# TB906_HW_V1.net
KiCad netlist of a schematic drawn in Altium Designer
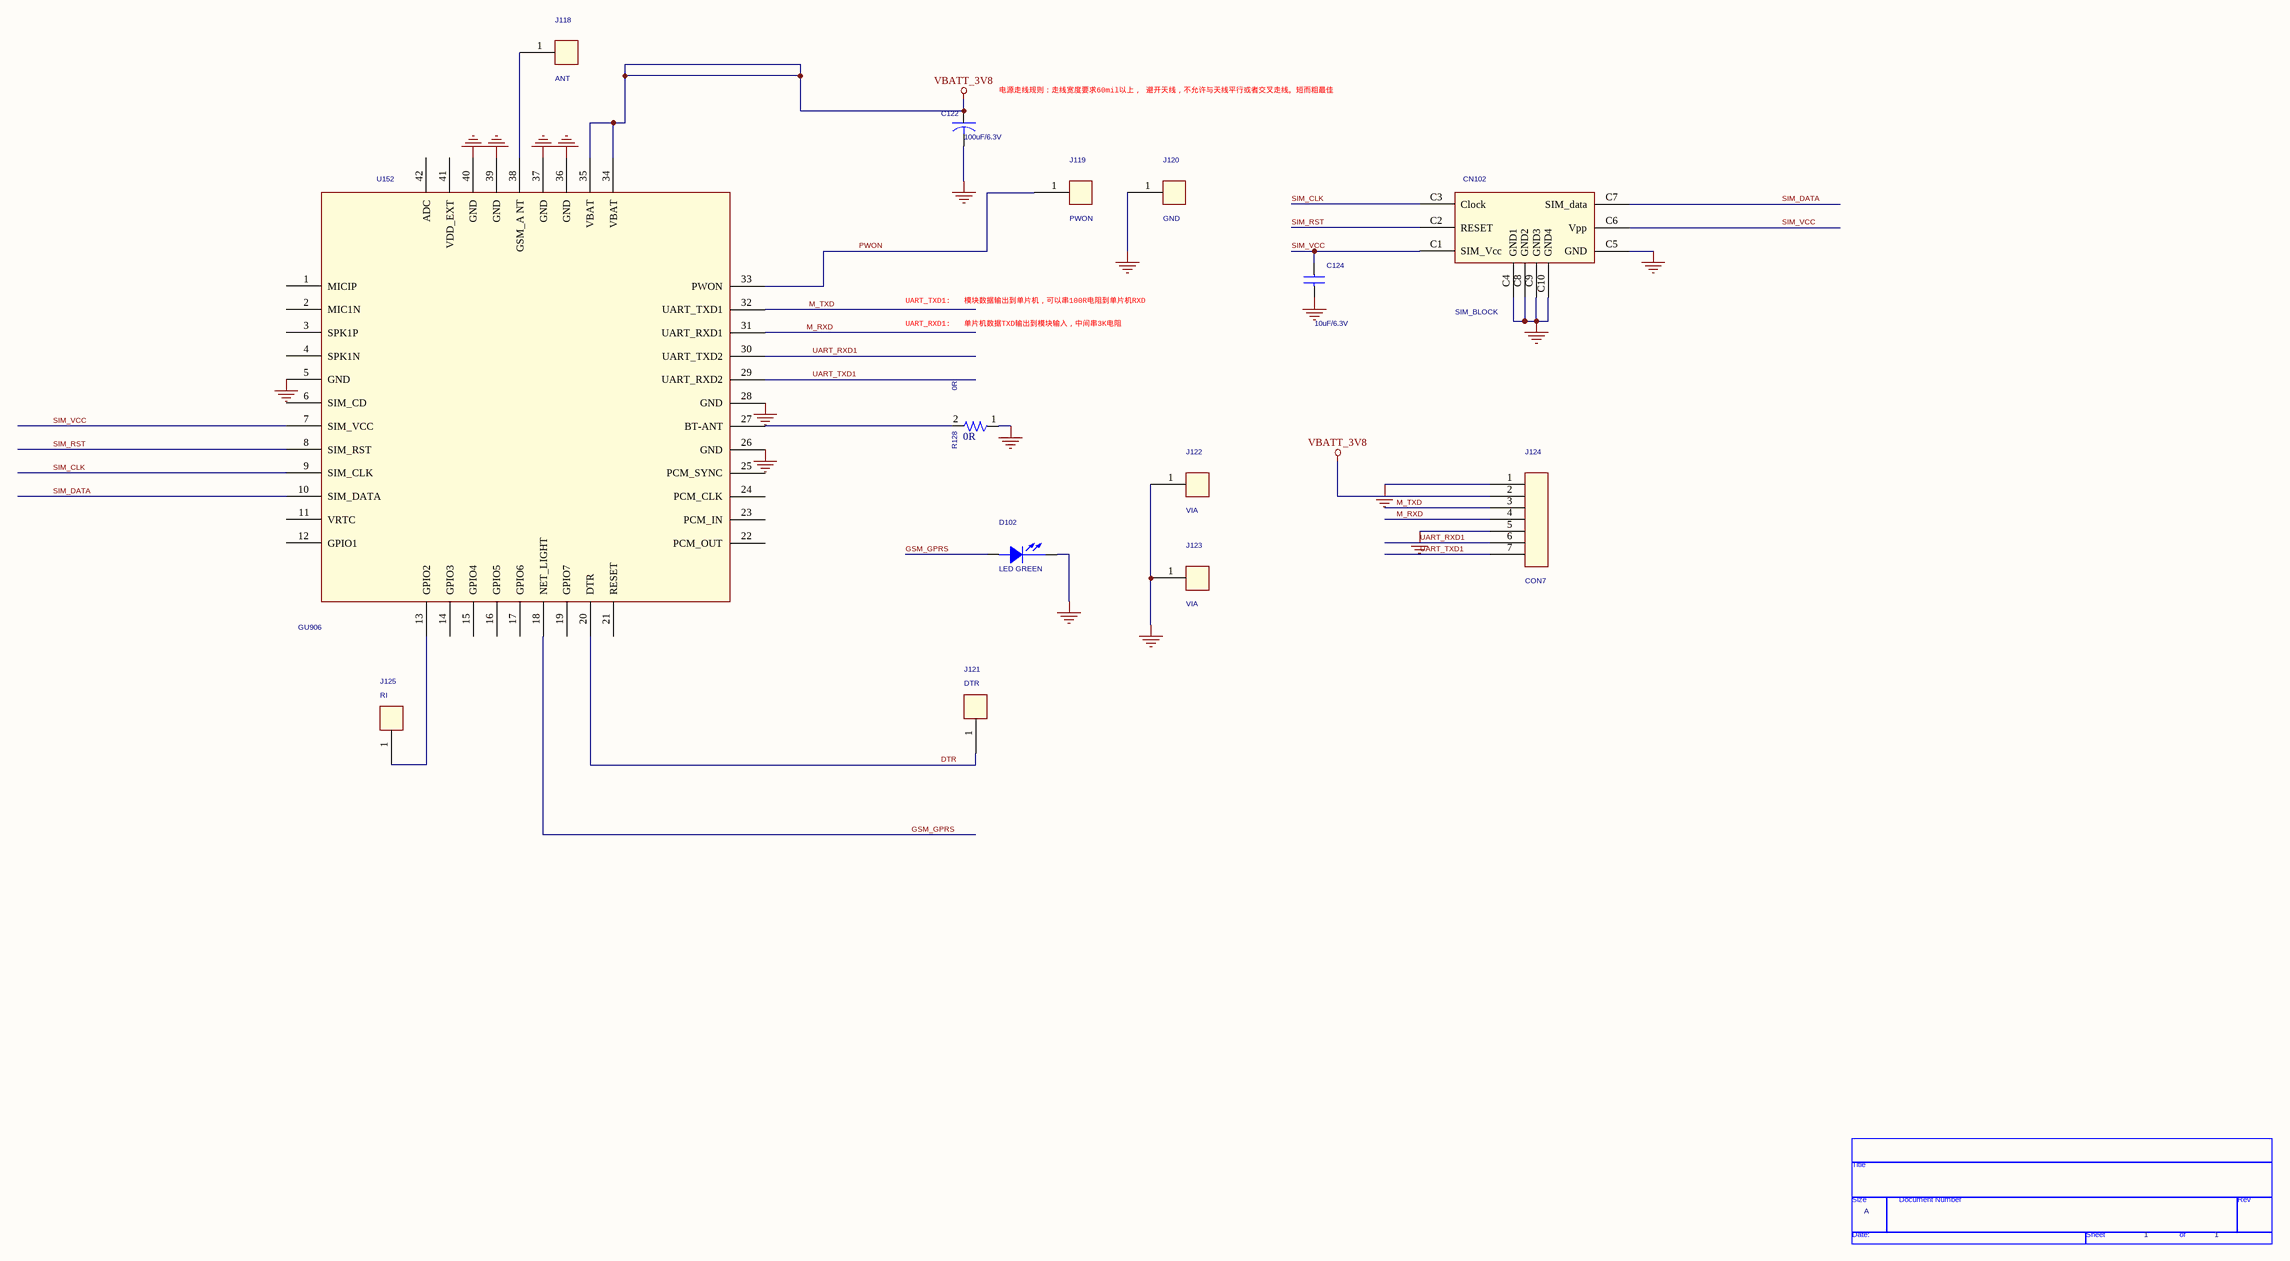
[diagram p0: TB906_HW V1.SchDoc]

(export (version "E")
  (design (tool "Eeschema 10.0.6"))
  (components
    (comp (ref "*")
      (value "TitleBlock0")
      (fields (field (name "PAGE COUNT") "1") (field (name "PAGE NUMBER") "1") (field (name "PAGE SIZE") "A"))
      (libsource (lib "*") (part "TitleBlock0"))
    )
    (comp (ref "C122") (value "100uF/6.3V") (libsource (lib "*") (part "CAP_5")))
    (comp (ref "C124") (value "10uF/6.3V") (libsource (lib "*") (part "CAP NP")))
    (comp (ref "CN102")
      (value "SIM_BLOCK")
      (footprint "SIM_BLOCK")
      (libsource (lib "*") (part "SIM_BLOCK_2"))
    )
    (comp (ref "D102") (value "LED GREEN") (libsource (lib "*") (part "LED")))
    (comp (ref "J118") (value "ANT") (libsource (lib "*") (part "CON1")))
    (comp (ref "J119") (value "PWON") (libsource (lib "*") (part "CON1")))
    (comp (ref "J120") (value "GND") (libsource (lib "*") (part "CON1")))
    (comp (ref "J121") (value "DTR") (libsource (lib "") (part "CON1_1")))
    (comp (ref "J122") (value "VIA") (libsource (lib "*") (part "CON1")))
    (comp (ref "J123") (value "VIA") (libsource (lib "*") (part "CON1")))
    (comp (ref "J124") (value "CON7") (libsource (lib "*") (part "CON7")))
    (comp (ref "J125") (value "RI") (libsource (lib "") (part "CON1_1")))
    (comp (ref "R128")
      (value "0R")
      (footprint "AX/RC05")
      (fields (field (name "ALTIUM_VALUE") "0R"))
      (libsource (lib "*") (part "r"))
    )
    (comp (ref "U152") (value "GU906") (libsource (lib "*") (part "GU600_LIB_2")))
  )
  (nets
    (net (code "1") (name "/DTR") (class "Default")
      (node (ref "J121") (pin "1") (pinfunction "1_1") (pintype "passive"))
      (node (ref "U152") (pin "20") (pinfunction "DTR_20") (pintype "passive"))
    )
    (net (code "2") (name "/GSM_GPRS") (class "Default")
      (node (ref "D102") (pin "1") (pinfunction "ANODE_1") (pintype "passive"))
      (node (ref "U152") (pin "18") (pinfunction "NET_LIGHT_18") (pintype "passive"))
    )
    (net (code "3") (name "/M_RXD") (class "Default")
      (node (ref "J124") (pin "4") (pinfunction "4_4") (pintype "passive"))
      (node (ref "U152") (pin "31") (pinfunction "UART_RXD1_31") (pintype "passive"))
    )
    (net (code "4") (name "/M_TXD") (class "Default")
      (node (ref "J124") (pin "3") (pinfunction "3_3") (pintype "passive"))
      (node (ref "U152") (pin "32") (pinfunction "UART_TXD1_32") (pintype "passive"))
    )
    (net (code "5") (name "/PWON") (class "Default")
      (node (ref "J119") (pin "1") (pinfunction "1_1") (pintype "passive"))
      (node (ref "U152") (pin "33") (pinfunction "PWON_33") (pintype "passive"))
    )
    (net (code "6") (name "/SIM_CLK") (class "Default")
      (node (ref "CN102") (pin "C3") (pinfunction "Clock_C3") (pintype "passive"))
      (node (ref "U152") (pin "9") (pinfunction "SIM_CLK_9") (pintype "passive"))
    )
    (net (code "7") (name "/SIM_DATA") (class "Default")
      (node (ref "CN102") (pin "C7") (pinfunction "SIM_data_C7") (pintype "passive"))
      (node (ref "U152") (pin "10") (pinfunction "SIM_DATA_10") (pintype "passive"))
    )
    (net (code "8") (name "/SIM_RST") (class "Default")
      (node (ref "CN102") (pin "C2") (pinfunction "RESET_C2") (pintype "passive"))
      (node (ref "U152") (pin "8") (pinfunction "SIM_RST_8") (pintype "passive"))
    )
    (net (code "9") (name "/SIM_VCC") (class "Default")
      (node (ref "C124") (pin "1") (pinfunction "1_1") (pintype "passive"))
      (node (ref "CN102") (pin "C1") (pinfunction "SIM_Vcc_C1") (pintype "passive"))
      (node (ref "CN102") (pin "C6") (pinfunction "Vpp_C6") (pintype "passive"))
      (node (ref "U152") (pin "7") (pinfunction "SIM_VCC_7") (pintype "passive"))
    )
    (net (code "10") (name "/UART_RXD1") (class "Default")
      (node (ref "J124") (pin "6") (pinfunction "6_6") (pintype "passive"))
      (node (ref "U152") (pin "30") (pinfunction "UART_TXD2_30") (pintype "passive"))
    )
    (net (code "11") (name "/UART_TXD1") (class "Default")
      (node (ref "J124") (pin "7") (pinfunction "7_7") (pintype "passive"))
      (node (ref "U152") (pin "29") (pinfunction "UART_RXD2_29") (pintype "passive"))
    )
    (net (code "12") (name "GND") (class "Default")
      (node (ref "C122") (pin "2") (pinfunction "2_2") (pintype "passive"))
      (node (ref "C124") (pin "2") (pinfunction "2_2") (pintype "passive"))
      (node (ref "CN102") (pin "C10") (pinfunction "GND4_C10") (pintype "passive"))
      (node (ref "CN102") (pin "C4") (pinfunction "GND1_C4") (pintype "passive"))
      (node (ref "CN102") (pin "C5") (pinfunction "GND_C5") (pintype "passive"))
      (node (ref "CN102") (pin "C8") (pinfunction "GND2_C8") (pintype "passive"))
      (node (ref "CN102") (pin "C9") (pinfunction "GND3_C9") (pintype "passive"))
      (node (ref "D102") (pin "2") (pinfunction "CATHODE_2") (pintype "passive"))
      (node (ref "J120") (pin "1") (pinfunction "1_1") (pintype "passive"))
      (node (ref "J122") (pin "1") (pinfunction "1_1") (pintype "passive"))
      (node (ref "J123") (pin "1") (pinfunction "1_1") (pintype "passive"))
      (node (ref "J124") (pin "1") (pinfunction "1_1") (pintype "passive"))
      (node (ref "J124") (pin "5") (pinfunction "5_5") (pintype "passive"))
      (node (ref "R128") (pin "1") (pinfunction "1_1") (pintype "passive"))
      (node (ref "U152") (pin "26") (pinfunction "GND_26") (pintype "passive"))
      (node (ref "U152") (pin "28") (pinfunction "GND_28") (pintype "passive"))
      (node (ref "U152") (pin "36") (pinfunction "GND_36") (pintype "passive"))
      (node (ref "U152") (pin "37") (pinfunction "GND_37") (pintype "passive"))
      (node (ref "U152") (pin "39") (pinfunction "GND_39") (pintype "passive"))
      (node (ref "U152") (pin "40") (pinfunction "GND_40") (pintype "passive"))
      (node (ref "U152") (pin "5") (pinfunction "GND_5") (pintype "passive"))
    )
    (net (code "13") (name "Net-(U152-BT-ANT)") (class "Default")
      (node (ref "R128") (pin "2") (pinfunction "2_2") (pintype "passive"))
      (node (ref "U152") (pin "27") (pinfunction "BT-ANT_27") (pintype "passive"))
    )
    (net (code "14") (name "Net-(U152-GPIO2)") (class "Default")
      (node (ref "J125") (pin "1") (pinfunction "1_1") (pintype "passive"))
      (node (ref "U152") (pin "13") (pinfunction "GPIO2_13") (pintype "passive"))
    )
    (net (code "15") (name "Net-(U152-GSM_A_NT)") (class "Default")
      (node (ref "J118") (pin "1") (pinfunction "1_1") (pintype "passive"))
      (node (ref "U152") (pin "38") (pinfunction "GSM_A_NT_38") (pintype "passive"))
    )
    (net (code "16") (name "VBATT_3V8") (class "Default")
      (node (ref "C122") (pin "1") (pinfunction "1_1") (pintype "passive"))
      (node (ref "J124") (pin "2") (pinfunction "2_2") (pintype "passive"))
      (node (ref "U152") (pin "34") (pinfunction "VBAT_34") (pintype "passive"))
      (node (ref "U152") (pin "35") (pinfunction "VBAT_35") (pintype "passive"))
    )
    (net (code "17") (name "unconnected-(U152-ADC-Pad42)") (class "Default")
      (node (ref "U152") (pin "42") (pinfunction "ADC_42") (pintype "passive"))
    )
    (net (code "18") (name "unconnected-(U152-GPIO1-Pad12)") (class "Default")
      (node (ref "U152") (pin "12") (pinfunction "GPIO1_12") (pintype "passive"))
    )
    (net (code "19") (name "unconnected-(U152-GPIO3-Pad14)") (class "Default")
      (node (ref "U152") (pin "14") (pinfunction "GPIO3_14") (pintype "passive"))
    )
    (net (code "20") (name "unconnected-(U152-GPIO4-Pad15)") (class "Default")
      (node (ref "U152") (pin "15") (pinfunction "GPIO4_15") (pintype "passive"))
    )
    (net (code "21") (name "unconnected-(U152-GPIO5-Pad16)") (class "Default")
      (node (ref "U152") (pin "16") (pinfunction "GPIO5_16") (pintype "passive"))
    )
    (net (code "22") (name "unconnected-(U152-GPIO6-Pad17)") (class "Default")
      (node (ref "U152") (pin "17") (pinfunction "GPIO6_17") (pintype "passive"))
    )
    (net (code "23") (name "unconnected-(U152-GPIO7-Pad19)") (class "Default")
      (node (ref "U152") (pin "19") (pinfunction "GPIO7_19") (pintype "passive"))
    )
    (net (code "24") (name "unconnected-(U152-MIC1N-Pad2)") (class "Default")
      (node (ref "U152") (pin "2") (pinfunction "MIC1N_2") (pintype "passive"))
    )
    (net (code "25") (name "unconnected-(U152-MICIP-Pad1)") (class "Default")
      (node (ref "U152") (pin "1") (pinfunction "MICIP_1") (pintype "passive"))
    )
    (net (code "26") (name "unconnected-(U152-PCM_CLK-Pad24)") (class "Default")
      (node (ref "U152") (pin "24") (pinfunction "PCM_CLK_24") (pintype "passive"))
    )
    (net (code "27") (name "unconnected-(U152-PCM_IN-Pad23)") (class "Default")
      (node (ref "U152") (pin "23") (pinfunction "PCM_IN_23") (pintype "passive"))
    )
    (net (code "28") (name "unconnected-(U152-PCM_OUT-Pad22)") (class "Default")
      (node (ref "U152") (pin "22") (pinfunction "PCM_OUT_22") (pintype "passive"))
    )
    (net (code "29") (name "unconnected-(U152-PCM_SYNC-Pad25)") (class "Default")
      (node (ref "U152") (pin "25") (pinfunction "PCM_SYNC_25") (pintype "passive"))
    )
    (net (code "30") (name "unconnected-(U152-RESET-Pad21)") (class "Default")
      (node (ref "U152") (pin "21") (pinfunction "RESET_21") (pintype "passive"))
    )
    (net (code "31") (name "unconnected-(U152-SIM_CD-Pad6)") (class "Default")
      (node (ref "U152") (pin "6") (pinfunction "SIM_CD_6") (pintype "passive"))
    )
    (net (code "32") (name "unconnected-(U152-SPK1N-Pad4)") (class "Default")
      (node (ref "U152") (pin "4") (pinfunction "SPK1N_4") (pintype "passive"))
    )
    (net (code "33") (name "unconnected-(U152-SPK1P-Pad3)") (class "Default")
      (node (ref "U152") (pin "3") (pinfunction "SPK1P_3") (pintype "passive"))
    )
    (net (code "34") (name "unconnected-(U152-VDD_EXT-Pad41)") (class "Default")
      (node (ref "U152") (pin "41") (pinfunction "VDD_EXT_41") (pintype "passive"))
    )
    (net (code "35") (name "unconnected-(U152-VRTC-Pad11)") (class "Default")
      (node (ref "U152") (pin "11") (pinfunction "VRTC_11") (pintype "passive"))
    )
  )
)
